# April.net
KiCad netlist of a schematic drawn in EAGLE
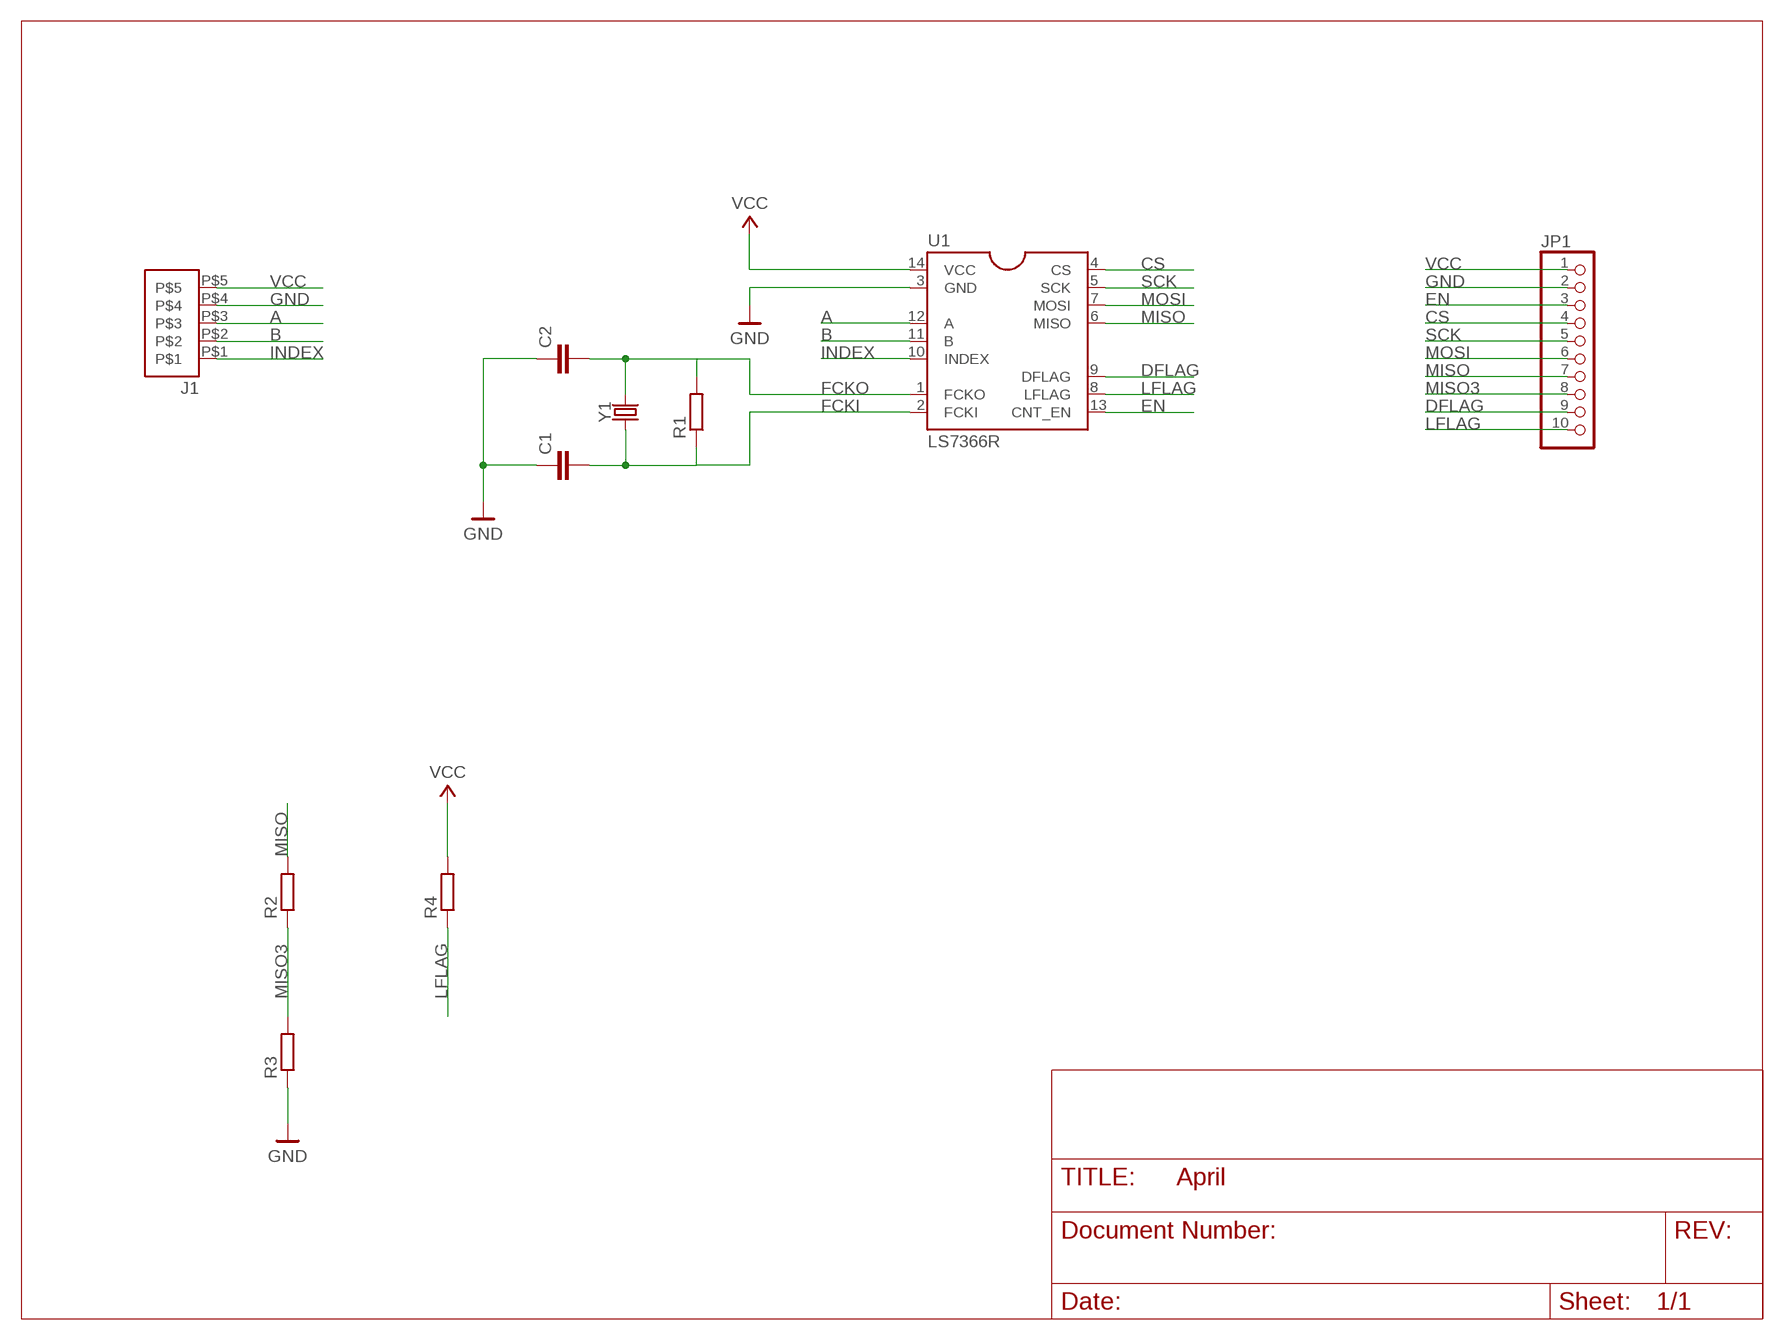
[diagram p0: schematic, sheet 1]

(export (version "E")
  (design (tool "Eeschema 10.0.6"))
  (components
    (comp (ref "C1")
      (value "C-EU050-024X044")
      (footprint "eagle-import:C050-024X044")
      (libsource (lib "eagle-import") (part "C-EU050-024X044"))
    )
    (comp (ref "C2")
      (value "C-EU050-024X044")
      (footprint "eagle-import:C050-024X044")
      (libsource (lib "eagle-import") (part "C-EU050-024X044"))
    )
    (comp (ref "J1")
      (value "AF-PID2319")
      (footprint "eagle-import:TB-01-5")
      (libsource (lib "eagle-import") (part "AF-PID2319"))
    )
    (comp (ref "JP1")
      (value "PINHD-1X10")
      (footprint "eagle-import:1X10")
      (libsource (lib "eagle-import") (part "PINHD-1X10"))
    )
    (comp (ref "R1")
      (value "R-EU_0207/10")
      (footprint "eagle-import:0207_10")
      (libsource (lib "eagle-import") (part "R-EU_0207/10"))
    )
    (comp (ref "R2")
      (value "R-EU_0207/10")
      (footprint "eagle-import:0207_10")
      (libsource (lib "eagle-import") (part "R-EU_0207/10"))
    )
    (comp (ref "R3")
      (value "R-EU_0207/10")
      (footprint "eagle-import:0207_10")
      (libsource (lib "eagle-import") (part "R-EU_0207/10"))
    )
    (comp (ref "R4")
      (value "R-EU_0207/10")
      (footprint "eagle-import:0207_10")
      (libsource (lib "eagle-import") (part "R-EU_0207/10"))
    )
    (comp (ref "U1")
      (value "LS7366R")
      (footprint "eagle-import:DIL14")
      (libsource (lib "eagle-import") (part "LS7366R"))
    )
    (comp (ref "Y1")
      (value "CRYSTALPTH-HC49US")
      (footprint "eagle-import:HC49US")
      (libsource (lib "eagle-import") (part "CRYSTALPTH-HC49US"))
    )
  )
  (nets
    (net (code "1") (name "/A") (class "Default")
      (node (ref "J1") (pin "P$3") (pinfunction "P$3_P$3") (pintype "bidirectional"))
      (node (ref "U1") (pin "12") (pinfunction "A_12") (pintype "input"))
    )
    (net (code "2") (name "/B") (class "Default")
      (node (ref "J1") (pin "P$2") (pinfunction "P$2_P$2") (pintype "bidirectional"))
      (node (ref "U1") (pin "11") (pinfunction "B_11") (pintype "input"))
    )
    (net (code "3") (name "/CS") (class "Default")
      (node (ref "JP1") (pin "4") (pinfunction "4_4") (pintype "passive"))
      (node (ref "U1") (pin "4") (pinfunction "CS_4") (pintype "input"))
    )
    (net (code "4") (name "/DFLAG") (class "Default")
      (node (ref "JP1") (pin "9") (pinfunction "9_9") (pintype "passive"))
      (node (ref "U1") (pin "9") (pinfunction "DFLAG_9") (pintype "output"))
    )
    (net (code "5") (name "/EN") (class "Default")
      (node (ref "JP1") (pin "3") (pinfunction "3_3") (pintype "passive"))
      (node (ref "U1") (pin "13") (pinfunction "CNT_EN_13") (pintype "input"))
    )
    (net (code "6") (name "/FCKI") (class "Default")
      (node (ref "C1") (pin "2") (pinfunction "2_2") (pintype "passive"))
      (node (ref "R1") (pin "1") (pinfunction "1_1") (pintype "passive"))
      (node (ref "U1") (pin "2") (pinfunction "FCKI_2") (pintype "input"))
      (node (ref "Y1") (pin "1") (pinfunction "1_1") (pintype "passive"))
    )
    (net (code "7") (name "/FCKO") (class "Default")
      (node (ref "C2") (pin "2") (pinfunction "2_2") (pintype "passive"))
      (node (ref "R1") (pin "2") (pinfunction "2_2") (pintype "passive"))
      (node (ref "U1") (pin "1") (pinfunction "FCKO_1") (pintype "output"))
      (node (ref "Y1") (pin "2") (pinfunction "2_2") (pintype "passive"))
    )
    (net (code "8") (name "/INDEX") (class "Default")
      (node (ref "J1") (pin "P$1") (pinfunction "P$1_P$1") (pintype "bidirectional"))
      (node (ref "U1") (pin "10") (pinfunction "INDEX_10") (pintype "input"))
    )
    (net (code "9") (name "/LFLAG") (class "Default")
      (node (ref "JP1") (pin "10") (pinfunction "10_10") (pintype "passive"))
      (node (ref "R4") (pin "1") (pinfunction "1_1") (pintype "passive"))
      (node (ref "U1") (pin "8") (pinfunction "LFLAG_8") (pintype "output"))
    )
    (net (code "10") (name "/MISO") (class "Default")
      (node (ref "JP1") (pin "7") (pinfunction "7_7") (pintype "passive"))
      (node (ref "R2") (pin "2") (pinfunction "2_2") (pintype "passive"))
      (node (ref "U1") (pin "6") (pinfunction "MISO_6") (pintype "output"))
    )
    (net (code "11") (name "/MISO3") (class "Default")
      (node (ref "JP1") (pin "8") (pinfunction "8_8") (pintype "passive"))
      (node (ref "R2") (pin "1") (pinfunction "1_1") (pintype "passive"))
      (node (ref "R3") (pin "2") (pinfunction "2_2") (pintype "passive"))
    )
    (net (code "12") (name "/MOSI") (class "Default")
      (node (ref "JP1") (pin "6") (pinfunction "6_6") (pintype "passive"))
      (node (ref "U1") (pin "7") (pinfunction "MOSI_7") (pintype "input"))
    )
    (net (code "13") (name "/SCK") (class "Default")
      (node (ref "JP1") (pin "5") (pinfunction "5_5") (pintype "passive"))
      (node (ref "U1") (pin "5") (pinfunction "SCK_5") (pintype "input"))
    )
    (net (code "14") (name "GND") (class "Default")
      (node (ref "C1") (pin "1") (pinfunction "1_1") (pintype "passive"))
      (node (ref "C2") (pin "1") (pinfunction "1_1") (pintype "passive"))
      (node (ref "J1") (pin "P$4") (pinfunction "P$4_P$4") (pintype "bidirectional"))
      (node (ref "JP1") (pin "2") (pinfunction "2_2") (pintype "passive"))
      (node (ref "R3") (pin "1") (pinfunction "1_1") (pintype "passive"))
      (node (ref "U1") (pin "3") (pinfunction "GND_3") (pintype "power_in"))
    )
    (net (code "15") (name "VCC") (class "Default")
      (node (ref "J1") (pin "P$5") (pinfunction "P$5_P$5") (pintype "bidirectional"))
      (node (ref "JP1") (pin "1") (pinfunction "1_1") (pintype "passive"))
      (node (ref "R4") (pin "2") (pinfunction "2_2") (pintype "passive"))
      (node (ref "U1") (pin "14") (pinfunction "VCC_14") (pintype "power_in"))
    )
  )
)
